# Capacitors.net
KiCad netlist of a schematic drawn in Altium Designer
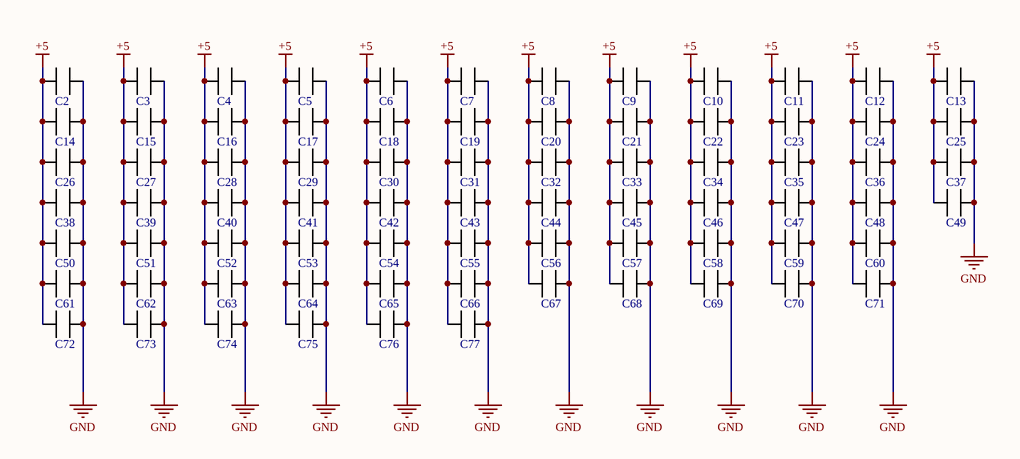
[diagram p0: Capacitors.SchDoc]

(export (version "E")
  (design (tool "Eeschema 10.0.6"))
  (components
    (comp (ref "C2")
      (value "100nF")
      (footprint "CAP_0402")
      (description "CAP_0402")
      (libsource (lib "Passives") (part "CAP_0402"))
    )
    (comp (ref "C3")
      (value "100nF")
      (footprint "CAP_0402")
      (description "CAP_0402")
      (libsource (lib "Passives") (part "CAP_0402"))
    )
    (comp (ref "C4")
      (value "100nF")
      (footprint "CAP_0402")
      (description "CAP_0402")
      (libsource (lib "Passives") (part "CAP_0402"))
    )
    (comp (ref "C5")
      (value "100nF")
      (footprint "CAP_0402")
      (description "CAP_0402")
      (libsource (lib "Passives") (part "CAP_0402"))
    )
    (comp (ref "C6")
      (value "100nF")
      (footprint "CAP_0402")
      (description "CAP_0402")
      (libsource (lib "Passives") (part "CAP_0402"))
    )
    (comp (ref "C7")
      (value "100nF")
      (footprint "CAP_0402")
      (description "CAP_0402")
      (libsource (lib "Passives") (part "CAP_0402"))
    )
    (comp (ref "C8")
      (value "100nF")
      (footprint "CAP_0402")
      (description "CAP_0402")
      (libsource (lib "Passives") (part "CAP_0402"))
    )
    (comp (ref "C9")
      (value "100nF")
      (footprint "CAP_0402")
      (description "CAP_0402")
      (libsource (lib "Passives") (part "CAP_0402"))
    )
    (comp (ref "C10")
      (value "100nF")
      (footprint "CAP_0402")
      (description "CAP_0402")
      (libsource (lib "Passives") (part "CAP_0402"))
    )
    (comp (ref "C11")
      (value "100nF")
      (footprint "CAP_0402")
      (description "CAP_0402")
      (libsource (lib "Passives") (part "CAP_0402"))
    )
    (comp (ref "C12")
      (value "100nF")
      (footprint "CAP_0402")
      (description "CAP_0402")
      (libsource (lib "Passives") (part "CAP_0402"))
    )
    (comp (ref "C13")
      (value "100nF")
      (footprint "CAP_0402")
      (description "CAP_0402")
      (libsource (lib "Passives") (part "CAP_0402"))
    )
    (comp (ref "C14")
      (value "100nF")
      (footprint "CAP_0402")
      (description "CAP_0402")
      (libsource (lib "Passives") (part "CAP_0402"))
    )
    (comp (ref "C15")
      (value "100nF")
      (footprint "CAP_0402")
      (description "CAP_0402")
      (libsource (lib "Passives") (part "CAP_0402"))
    )
    (comp (ref "C16")
      (value "100nF")
      (footprint "CAP_0402")
      (description "CAP_0402")
      (libsource (lib "Passives") (part "CAP_0402"))
    )
    (comp (ref "C17")
      (value "100nF")
      (footprint "CAP_0402")
      (description "CAP_0402")
      (libsource (lib "Passives") (part "CAP_0402"))
    )
    (comp (ref "C18")
      (value "100nF")
      (footprint "CAP_0402")
      (description "CAP_0402")
      (libsource (lib "Passives") (part "CAP_0402"))
    )
    (comp (ref "C19")
      (value "100nF")
      (footprint "CAP_0402")
      (description "CAP_0402")
      (libsource (lib "Passives") (part "CAP_0402"))
    )
    (comp (ref "C20")
      (value "100nF")
      (footprint "CAP_0402")
      (description "CAP_0402")
      (libsource (lib "Passives") (part "CAP_0402"))
    )
    (comp (ref "C21")
      (value "100nF")
      (footprint "CAP_0402")
      (description "CAP_0402")
      (libsource (lib "Passives") (part "CAP_0402"))
    )
    (comp (ref "C22")
      (value "100nF")
      (footprint "CAP_0402")
      (description "CAP_0402")
      (libsource (lib "Passives") (part "CAP_0402"))
    )
    (comp (ref "C23")
      (value "100nF")
      (footprint "CAP_0402")
      (description "CAP_0402")
      (libsource (lib "Passives") (part "CAP_0402"))
    )
    (comp (ref "C24")
      (value "100nF")
      (footprint "CAP_0402")
      (description "CAP_0402")
      (libsource (lib "Passives") (part "CAP_0402"))
    )
    (comp (ref "C25")
      (value "100nF")
      (footprint "CAP_0402")
      (description "CAP_0402")
      (libsource (lib "Passives") (part "CAP_0402"))
    )
    (comp (ref "C26")
      (value "100nF")
      (footprint "CAP_0402")
      (description "CAP_0402")
      (libsource (lib "Passives") (part "CAP_0402"))
    )
    (comp (ref "C27")
      (value "100nF")
      (footprint "CAP_0402")
      (description "CAP_0402")
      (libsource (lib "Passives") (part "CAP_0402"))
    )
    (comp (ref "C28")
      (value "100nF")
      (footprint "CAP_0402")
      (description "CAP_0402")
      (libsource (lib "Passives") (part "CAP_0402"))
    )
    (comp (ref "C29")
      (value "100nF")
      (footprint "CAP_0402")
      (description "CAP_0402")
      (libsource (lib "Passives") (part "CAP_0402"))
    )
    (comp (ref "C30")
      (value "100nF")
      (footprint "CAP_0402")
      (description "CAP_0402")
      (libsource (lib "Passives") (part "CAP_0402"))
    )
    (comp (ref "C31")
      (value "100nF")
      (footprint "CAP_0402")
      (description "CAP_0402")
      (libsource (lib "Passives") (part "CAP_0402"))
    )
    (comp (ref "C32")
      (value "100nF")
      (footprint "CAP_0402")
      (description "CAP_0402")
      (libsource (lib "Passives") (part "CAP_0402"))
    )
    (comp (ref "C33")
      (value "100nF")
      (footprint "CAP_0402")
      (description "CAP_0402")
      (libsource (lib "Passives") (part "CAP_0402"))
    )
    (comp (ref "C34")
      (value "100nF")
      (footprint "CAP_0402")
      (description "CAP_0402")
      (libsource (lib "Passives") (part "CAP_0402"))
    )
    (comp (ref "C35")
      (value "100nF")
      (footprint "CAP_0402")
      (description "CAP_0402")
      (libsource (lib "Passives") (part "CAP_0402"))
    )
    (comp (ref "C36")
      (value "100nF")
      (footprint "CAP_0402")
      (description "CAP_0402")
      (libsource (lib "Passives") (part "CAP_0402"))
    )
    (comp (ref "C37")
      (value "100nF")
      (footprint "CAP_0402")
      (description "CAP_0402")
      (libsource (lib "Passives") (part "CAP_0402"))
    )
    (comp (ref "C38")
      (value "100nF")
      (footprint "CAP_0402")
      (description "CAP_0402")
      (libsource (lib "Passives") (part "CAP_0402"))
    )
    (comp (ref "C39")
      (value "100nF")
      (footprint "CAP_0402")
      (description "CAP_0402")
      (libsource (lib "Passives") (part "CAP_0402"))
    )
    (comp (ref "C40")
      (value "100nF")
      (footprint "CAP_0402")
      (description "CAP_0402")
      (libsource (lib "Passives") (part "CAP_0402"))
    )
    (comp (ref "C41")
      (value "100nF")
      (footprint "CAP_0402")
      (description "CAP_0402")
      (libsource (lib "Passives") (part "CAP_0402"))
    )
    (comp (ref "C42")
      (value "100nF")
      (footprint "CAP_0402")
      (description "CAP_0402")
      (libsource (lib "Passives") (part "CAP_0402"))
    )
    (comp (ref "C43")
      (value "100nF")
      (footprint "CAP_0402")
      (description "CAP_0402")
      (libsource (lib "Passives") (part "CAP_0402"))
    )
    (comp (ref "C44")
      (value "100nF")
      (footprint "CAP_0402")
      (description "CAP_0402")
      (libsource (lib "Passives") (part "CAP_0402"))
    )
    (comp (ref "C45")
      (value "100nF")
      (footprint "CAP_0402")
      (description "CAP_0402")
      (libsource (lib "Passives") (part "CAP_0402"))
    )
    (comp (ref "C46")
      (value "100nF")
      (footprint "CAP_0402")
      (description "CAP_0402")
      (libsource (lib "Passives") (part "CAP_0402"))
    )
    (comp (ref "C47")
      (value "100nF")
      (footprint "CAP_0402")
      (description "CAP_0402")
      (libsource (lib "Passives") (part "CAP_0402"))
    )
    (comp (ref "C48")
      (value "100nF")
      (footprint "CAP_0402")
      (description "CAP_0402")
      (libsource (lib "Passives") (part "CAP_0402"))
    )
    (comp (ref "C49")
      (value "100nF")
      (footprint "CAP_0402")
      (description "CAP_0402")
      (libsource (lib "Passives") (part "CAP_0402"))
    )
    (comp (ref "C50")
      (value "100nF")
      (footprint "CAP_0402")
      (description "CAP_0402")
      (libsource (lib "Passives") (part "CAP_0402"))
    )
    (comp (ref "C51")
      (value "100nF")
      (footprint "CAP_0402")
      (description "CAP_0402")
      (libsource (lib "Passives") (part "CAP_0402"))
    )
    (comp (ref "C52")
      (value "100nF")
      (footprint "CAP_0402")
      (description "CAP_0402")
      (libsource (lib "Passives") (part "CAP_0402"))
    )
    (comp (ref "C53")
      (value "100nF")
      (footprint "CAP_0402")
      (description "CAP_0402")
      (libsource (lib "Passives") (part "CAP_0402"))
    )
    (comp (ref "C54")
      (value "100nF")
      (footprint "CAP_0402")
      (description "CAP_0402")
      (libsource (lib "Passives") (part "CAP_0402"))
    )
    (comp (ref "C55")
      (value "100nF")
      (footprint "CAP_0402")
      (description "CAP_0402")
      (libsource (lib "Passives") (part "CAP_0402"))
    )
    (comp (ref "C56")
      (value "100nF")
      (footprint "CAP_0402")
      (description "CAP_0402")
      (libsource (lib "Passives") (part "CAP_0402"))
    )
    (comp (ref "C57")
      (value "100nF")
      (footprint "CAP_0402")
      (description "CAP_0402")
      (libsource (lib "Passives") (part "CAP_0402"))
    )
    (comp (ref "C58")
      (value "100nF")
      (footprint "CAP_0402")
      (description "CAP_0402")
      (libsource (lib "Passives") (part "CAP_0402"))
    )
    (comp (ref "C59")
      (value "100nF")
      (footprint "CAP_0402")
      (description "CAP_0402")
      (libsource (lib "Passives") (part "CAP_0402"))
    )
    (comp (ref "C60")
      (value "100nF")
      (footprint "CAP_0402")
      (description "CAP_0402")
      (libsource (lib "Passives") (part "CAP_0402"))
    )
    (comp (ref "C61")
      (value "100nF")
      (footprint "CAP_0402")
      (description "CAP_0402")
      (libsource (lib "Passives") (part "CAP_0402"))
    )
    (comp (ref "C62")
      (value "100nF")
      (footprint "CAP_0402")
      (description "CAP_0402")
      (libsource (lib "Passives") (part "CAP_0402"))
    )
    (comp (ref "C63")
      (value "100nF")
      (footprint "CAP_0402")
      (description "CAP_0402")
      (libsource (lib "Passives") (part "CAP_0402"))
    )
    (comp (ref "C64")
      (value "100nF")
      (footprint "CAP_0402")
      (description "CAP_0402")
      (libsource (lib "Passives") (part "CAP_0402"))
    )
    (comp (ref "C65")
      (value "100nF")
      (footprint "CAP_0402")
      (description "CAP_0402")
      (libsource (lib "Passives") (part "CAP_0402"))
    )
    (comp (ref "C66")
      (value "100nF")
      (footprint "CAP_0402")
      (description "CAP_0402")
      (libsource (lib "Passives") (part "CAP_0402"))
    )
    (comp (ref "C67")
      (value "100nF")
      (footprint "CAP_0402")
      (description "CAP_0402")
      (libsource (lib "Passives") (part "CAP_0402"))
    )
    (comp (ref "C68")
      (value "100nF")
      (footprint "CAP_0402")
      (description "CAP_0402")
      (libsource (lib "Passives") (part "CAP_0402"))
    )
    (comp (ref "C69")
      (value "100nF")
      (footprint "CAP_0402")
      (description "CAP_0402")
      (libsource (lib "Passives") (part "CAP_0402"))
    )
    (comp (ref "C70")
      (value "100nF")
      (footprint "CAP_0402")
      (description "CAP_0402")
      (libsource (lib "Passives") (part "CAP_0402"))
    )
    (comp (ref "C71")
      (value "100nF")
      (footprint "CAP_0402")
      (description "CAP_0402")
      (libsource (lib "Passives") (part "CAP_0402"))
    )
    (comp (ref "C72")
      (value "100nF")
      (footprint "CAP_0402")
      (description "CAP_0402")
      (libsource (lib "Passives") (part "CAP_0402"))
    )
    (comp (ref "C73")
      (value "100nF")
      (footprint "CAP_0402")
      (description "CAP_0402")
      (libsource (lib "Passives") (part "CAP_0402"))
    )
    (comp (ref "C74")
      (value "100nF")
      (footprint "CAP_0402")
      (description "CAP_0402")
      (libsource (lib "Passives") (part "CAP_0402"))
    )
    (comp (ref "C75")
      (value "100nF")
      (footprint "CAP_0402")
      (description "CAP_0402")
      (libsource (lib "Passives") (part "CAP_0402"))
    )
    (comp (ref "C76")
      (value "100nF")
      (footprint "CAP_0402")
      (description "CAP_0402")
      (libsource (lib "Passives") (part "CAP_0402"))
    )
    (comp (ref "C77")
      (value "100nF")
      (footprint "CAP_0402")
      (description "CAP_0402")
      (libsource (lib "Passives") (part "CAP_0402"))
    )
  )
  (nets
    (net (code "1") (name "+5") (class "Default")
      (node (ref "C10") (pin "1") (pinfunction "1_1") (pintype "passive"))
      (node (ref "C11") (pin "1") (pinfunction "1_1") (pintype "passive"))
      (node (ref "C12") (pin "1") (pinfunction "1_1") (pintype "passive"))
      (node (ref "C13") (pin "1") (pinfunction "1_1") (pintype "passive"))
      (node (ref "C14") (pin "1") (pinfunction "1_1") (pintype "passive"))
      (node (ref "C15") (pin "1") (pinfunction "1_1") (pintype "passive"))
      (node (ref "C16") (pin "1") (pinfunction "1_1") (pintype "passive"))
      (node (ref "C17") (pin "1") (pinfunction "1_1") (pintype "passive"))
      (node (ref "C18") (pin "1") (pinfunction "1_1") (pintype "passive"))
      (node (ref "C19") (pin "1") (pinfunction "1_1") (pintype "passive"))
      (node (ref "C2") (pin "1") (pinfunction "1_1") (pintype "passive"))
      (node (ref "C20") (pin "1") (pinfunction "1_1") (pintype "passive"))
      (node (ref "C21") (pin "1") (pinfunction "1_1") (pintype "passive"))
      (node (ref "C22") (pin "1") (pinfunction "1_1") (pintype "passive"))
      (node (ref "C23") (pin "1") (pinfunction "1_1") (pintype "passive"))
      (node (ref "C24") (pin "1") (pinfunction "1_1") (pintype "passive"))
      (node (ref "C25") (pin "1") (pinfunction "1_1") (pintype "passive"))
      (node (ref "C26") (pin "1") (pinfunction "1_1") (pintype "passive"))
      (node (ref "C27") (pin "1") (pinfunction "1_1") (pintype "passive"))
      (node (ref "C28") (pin "1") (pinfunction "1_1") (pintype "passive"))
      (node (ref "C29") (pin "1") (pinfunction "1_1") (pintype "passive"))
      (node (ref "C3") (pin "1") (pinfunction "1_1") (pintype "passive"))
      (node (ref "C30") (pin "1") (pinfunction "1_1") (pintype "passive"))
      (node (ref "C31") (pin "1") (pinfunction "1_1") (pintype "passive"))
      (node (ref "C32") (pin "1") (pinfunction "1_1") (pintype "passive"))
      (node (ref "C33") (pin "1") (pinfunction "1_1") (pintype "passive"))
      (node (ref "C34") (pin "1") (pinfunction "1_1") (pintype "passive"))
      (node (ref "C35") (pin "1") (pinfunction "1_1") (pintype "passive"))
      (node (ref "C36") (pin "1") (pinfunction "1_1") (pintype "passive"))
      (node (ref "C37") (pin "1") (pinfunction "1_1") (pintype "passive"))
      (node (ref "C38") (pin "1") (pinfunction "1_1") (pintype "passive"))
      (node (ref "C39") (pin "1") (pinfunction "1_1") (pintype "passive"))
      (node (ref "C4") (pin "1") (pinfunction "1_1") (pintype "passive"))
      (node (ref "C40") (pin "1") (pinfunction "1_1") (pintype "passive"))
      (node (ref "C41") (pin "1") (pinfunction "1_1") (pintype "passive"))
      (node (ref "C42") (pin "1") (pinfunction "1_1") (pintype "passive"))
      (node (ref "C43") (pin "1") (pinfunction "1_1") (pintype "passive"))
      (node (ref "C44") (pin "1") (pinfunction "1_1") (pintype "passive"))
      (node (ref "C45") (pin "1") (pinfunction "1_1") (pintype "passive"))
      (node (ref "C46") (pin "1") (pinfunction "1_1") (pintype "passive"))
      (node (ref "C47") (pin "1") (pinfunction "1_1") (pintype "passive"))
      (node (ref "C48") (pin "1") (pinfunction "1_1") (pintype "passive"))
      (node (ref "C49") (pin "1") (pinfunction "1_1") (pintype "passive"))
      (node (ref "C5") (pin "1") (pinfunction "1_1") (pintype "passive"))
      (node (ref "C50") (pin "1") (pinfunction "1_1") (pintype "passive"))
      (node (ref "C51") (pin "1") (pinfunction "1_1") (pintype "passive"))
      (node (ref "C52") (pin "1") (pinfunction "1_1") (pintype "passive"))
      (node (ref "C53") (pin "1") (pinfunction "1_1") (pintype "passive"))
      (node (ref "C54") (pin "1") (pinfunction "1_1") (pintype "passive"))
      (node (ref "C55") (pin "1") (pinfunction "1_1") (pintype "passive"))
      (node (ref "C56") (pin "1") (pinfunction "1_1") (pintype "passive"))
      (node (ref "C57") (pin "1") (pinfunction "1_1") (pintype "passive"))
      (node (ref "C58") (pin "1") (pinfunction "1_1") (pintype "passive"))
      (node (ref "C59") (pin "1") (pinfunction "1_1") (pintype "passive"))
      (node (ref "C6") (pin "1") (pinfunction "1_1") (pintype "passive"))
      (node (ref "C60") (pin "1") (pinfunction "1_1") (pintype "passive"))
      (node (ref "C61") (pin "1") (pinfunction "1_1") (pintype "passive"))
      (node (ref "C62") (pin "1") (pinfunction "1_1") (pintype "passive"))
      (node (ref "C63") (pin "1") (pinfunction "1_1") (pintype "passive"))
      (node (ref "C64") (pin "1") (pinfunction "1_1") (pintype "passive"))
      (node (ref "C65") (pin "1") (pinfunction "1_1") (pintype "passive"))
      (node (ref "C66") (pin "1") (pinfunction "1_1") (pintype "passive"))
      (node (ref "C67") (pin "1") (pinfunction "1_1") (pintype "passive"))
      (node (ref "C68") (pin "1") (pinfunction "1_1") (pintype "passive"))
      (node (ref "C69") (pin "1") (pinfunction "1_1") (pintype "passive"))
      (node (ref "C7") (pin "1") (pinfunction "1_1") (pintype "passive"))
      (node (ref "C70") (pin "1") (pinfunction "1_1") (pintype "passive"))
      (node (ref "C71") (pin "1") (pinfunction "1_1") (pintype "passive"))
      (node (ref "C72") (pin "1") (pinfunction "1_1") (pintype "passive"))
      (node (ref "C73") (pin "1") (pinfunction "1_1") (pintype "passive"))
      (node (ref "C74") (pin "1") (pinfunction "1_1") (pintype "passive"))
      (node (ref "C75") (pin "1") (pinfunction "1_1") (pintype "passive"))
      (node (ref "C76") (pin "1") (pinfunction "1_1") (pintype "passive"))
      (node (ref "C77") (pin "1") (pinfunction "1_1") (pintype "passive"))
      (node (ref "C8") (pin "1") (pinfunction "1_1") (pintype "passive"))
      (node (ref "C9") (pin "1") (pinfunction "1_1") (pintype "passive"))
    )
    (net (code "2") (name "GND") (class "Default")
      (node (ref "C10") (pin "2") (pinfunction "2_2") (pintype "passive"))
      (node (ref "C11") (pin "2") (pinfunction "2_2") (pintype "passive"))
      (node (ref "C12") (pin "2") (pinfunction "2_2") (pintype "passive"))
      (node (ref "C13") (pin "2") (pinfunction "2_2") (pintype "passive"))
      (node (ref "C14") (pin "2") (pinfunction "2_2") (pintype "passive"))
      (node (ref "C15") (pin "2") (pinfunction "2_2") (pintype "passive"))
      (node (ref "C16") (pin "2") (pinfunction "2_2") (pintype "passive"))
      (node (ref "C17") (pin "2") (pinfunction "2_2") (pintype "passive"))
      (node (ref "C18") (pin "2") (pinfunction "2_2") (pintype "passive"))
      (node (ref "C19") (pin "2") (pinfunction "2_2") (pintype "passive"))
      (node (ref "C2") (pin "2") (pinfunction "2_2") (pintype "passive"))
      (node (ref "C20") (pin "2") (pinfunction "2_2") (pintype "passive"))
      (node (ref "C21") (pin "2") (pinfunction "2_2") (pintype "passive"))
      (node (ref "C22") (pin "2") (pinfunction "2_2") (pintype "passive"))
      (node (ref "C23") (pin "2") (pinfunction "2_2") (pintype "passive"))
      (node (ref "C24") (pin "2") (pinfunction "2_2") (pintype "passive"))
      (node (ref "C25") (pin "2") (pinfunction "2_2") (pintype "passive"))
      (node (ref "C26") (pin "2") (pinfunction "2_2") (pintype "passive"))
      (node (ref "C27") (pin "2") (pinfunction "2_2") (pintype "passive"))
      (node (ref "C28") (pin "2") (pinfunction "2_2") (pintype "passive"))
      (node (ref "C29") (pin "2") (pinfunction "2_2") (pintype "passive"))
      (node (ref "C3") (pin "2") (pinfunction "2_2") (pintype "passive"))
      (node (ref "C30") (pin "2") (pinfunction "2_2") (pintype "passive"))
      (node (ref "C31") (pin "2") (pinfunction "2_2") (pintype "passive"))
      (node (ref "C32") (pin "2") (pinfunction "2_2") (pintype "passive"))
      (node (ref "C33") (pin "2") (pinfunction "2_2") (pintype "passive"))
      (node (ref "C34") (pin "2") (pinfunction "2_2") (pintype "passive"))
      (node (ref "C35") (pin "2") (pinfunction "2_2") (pintype "passive"))
      (node (ref "C36") (pin "2") (pinfunction "2_2") (pintype "passive"))
      (node (ref "C37") (pin "2") (pinfunction "2_2") (pintype "passive"))
      (node (ref "C38") (pin "2") (pinfunction "2_2") (pintype "passive"))
      (node (ref "C39") (pin "2") (pinfunction "2_2") (pintype "passive"))
      (node (ref "C4") (pin "2") (pinfunction "2_2") (pintype "passive"))
      (node (ref "C40") (pin "2") (pinfunction "2_2") (pintype "passive"))
      (node (ref "C41") (pin "2") (pinfunction "2_2") (pintype "passive"))
      (node (ref "C42") (pin "2") (pinfunction "2_2") (pintype "passive"))
      (node (ref "C43") (pin "2") (pinfunction "2_2") (pintype "passive"))
      (node (ref "C44") (pin "2") (pinfunction "2_2") (pintype "passive"))
      (node (ref "C45") (pin "2") (pinfunction "2_2") (pintype "passive"))
      (node (ref "C46") (pin "2") (pinfunction "2_2") (pintype "passive"))
      (node (ref "C47") (pin "2") (pinfunction "2_2") (pintype "passive"))
      (node (ref "C48") (pin "2") (pinfunction "2_2") (pintype "passive"))
      (node (ref "C49") (pin "2") (pinfunction "2_2") (pintype "passive"))
      (node (ref "C5") (pin "2") (pinfunction "2_2") (pintype "passive"))
      (node (ref "C50") (pin "2") (pinfunction "2_2") (pintype "passive"))
      (node (ref "C51") (pin "2") (pinfunction "2_2") (pintype "passive"))
      (node (ref "C52") (pin "2") (pinfunction "2_2") (pintype "passive"))
      (node (ref "C53") (pin "2") (pinfunction "2_2") (pintype "passive"))
      (node (ref "C54") (pin "2") (pinfunction "2_2") (pintype "passive"))
      (node (ref "C55") (pin "2") (pinfunction "2_2") (pintype "passive"))
      (node (ref "C56") (pin "2") (pinfunction "2_2") (pintype "passive"))
      (node (ref "C57") (pin "2") (pinfunction "2_2") (pintype "passive"))
      (node (ref "C58") (pin "2") (pinfunction "2_2") (pintype "passive"))
      (node (ref "C59") (pin "2") (pinfunction "2_2") (pintype "passive"))
      (node (ref "C6") (pin "2") (pinfunction "2_2") (pintype "passive"))
      (node (ref "C60") (pin "2") (pinfunction "2_2") (pintype "passive"))
      (node (ref "C61") (pin "2") (pinfunction "2_2") (pintype "passive"))
      (node (ref "C62") (pin "2") (pinfunction "2_2") (pintype "passive"))
      (node (ref "C63") (pin "2") (pinfunction "2_2") (pintype "passive"))
      (node (ref "C64") (pin "2") (pinfunction "2_2") (pintype "passive"))
      (node (ref "C65") (pin "2") (pinfunction "2_2") (pintype "passive"))
      (node (ref "C66") (pin "2") (pinfunction "2_2") (pintype "passive"))
      (node (ref "C67") (pin "2") (pinfunction "2_2") (pintype "passive"))
      (node (ref "C68") (pin "2") (pinfunction "2_2") (pintype "passive"))
      (node (ref "C69") (pin "2") (pinfunction "2_2") (pintype "passive"))
      (node (ref "C7") (pin "2") (pinfunction "2_2") (pintype "passive"))
      (node (ref "C70") (pin "2") (pinfunction "2_2") (pintype "passive"))
      (node (ref "C71") (pin "2") (pinfunction "2_2") (pintype "passive"))
      (node (ref "C72") (pin "2") (pinfunction "2_2") (pintype "passive"))
      (node (ref "C73") (pin "2") (pinfunction "2_2") (pintype "passive"))
      (node (ref "C74") (pin "2") (pinfunction "2_2") (pintype "passive"))
      (node (ref "C75") (pin "2") (pinfunction "2_2") (pintype "passive"))
      (node (ref "C76") (pin "2") (pinfunction "2_2") (pintype "passive"))
      (node (ref "C77") (pin "2") (pinfunction "2_2") (pintype "passive"))
      (node (ref "C8") (pin "2") (pinfunction "2_2") (pintype "passive"))
      (node (ref "C9") (pin "2") (pinfunction "2_2") (pintype "passive"))
    )
  )
)
